# connecting.net
KiCad netlist of a schematic drawn in EAGLE
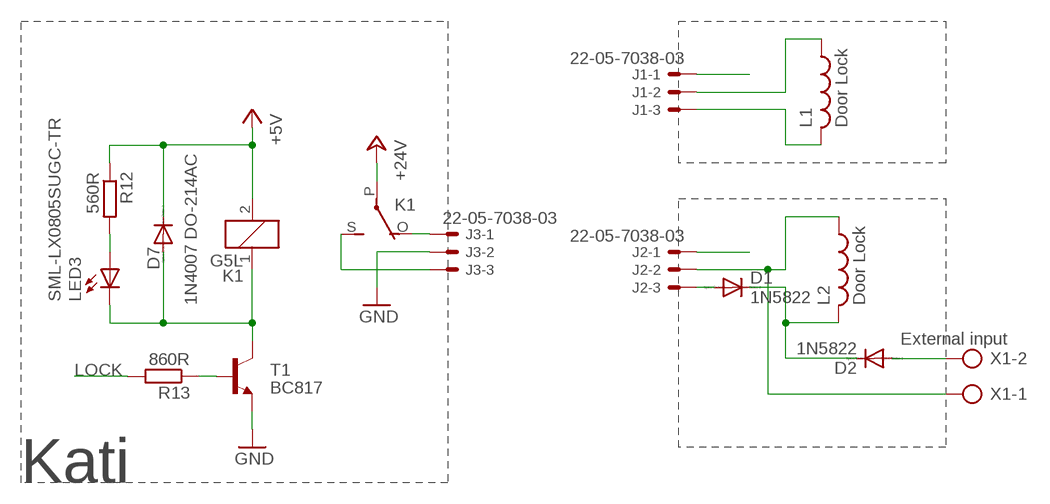
[diagram p0: schematic, sheet 1]

(export (version "E")
  (design (tool "Eeschema 10.0.6"))
  (components
    (comp (ref "D1")
      (value "1N5822")
      (footprint "eagle-import:DO204-10")
      (libsource (lib "eagle-import") (part "1N5059"))
    )
    (comp (ref "D2")
      (value "1N5822")
      (footprint "eagle-import:DO204-10")
      (libsource (lib "eagle-import") (part "1N5059"))
    )
    (comp (ref "D7")
      (value "1N4007 DO-214AC")
      (footprint "eagle-import:DO-214AC")
      (libsource (lib "eagle-import") (part "DIODE-DO-214AC"))
    )
    (comp (ref "J1")
      (value "22-05-7038-03")
      (footprint "eagle-import:7395-03")
      (libsource (lib "eagle-import") (part "22-?-0305-7038"))
    )
    (comp (ref "J2")
      (value "22-05-7038-03")
      (footprint "eagle-import:7395-03")
      (libsource (lib "eagle-import") (part "22-?-0305-7038"))
    )
    (comp (ref "J3")
      (value "22-05-7038-03")
      (footprint "eagle-import:7395-03")
      (libsource (lib "eagle-import") (part "22-?-0305-7038"))
    )
    (comp (ref "K1")
      (value "G5L")
      (footprint "eagle-import:G5LE")
      (libsource (lib "eagle-import") (part "G5L"))
    )
    (comp (ref "L1")
      (value "Door Lock")
      (footprint "eagle-import:0204_5")
      (libsource (lib "eagle-import") (part "L-US0204/5"))
    )
    (comp (ref "L2")
      (value "Door Lock")
      (footprint "eagle-import:0204_5")
      (libsource (lib "eagle-import") (part "L-US0204/5"))
    )
    (comp (ref "LED3")
      (value "SML-LX0805SUGC-TR")
      (footprint "eagle-import:CHIPLED_0805")
      (libsource (lib "eagle-import") (part "LEDCHIPLED_0805"))
    )
    (comp (ref "R12")
      (value "560R")
      (footprint "eagle-import:R0805")
      (libsource (lib "eagle-import") (part "R-EU_R0805"))
    )
    (comp (ref "R13")
      (value "860R")
      (footprint "eagle-import:R0805")
      (libsource (lib "eagle-import") (part "R-EU_R0805"))
    )
    (comp (ref "T1")
      (value "BC817")
      (footprint "eagle-import:SOT23-BEC")
      (libsource (lib "eagle-import") (part "-NPN-SOT23-BECBC817-16"))
    )
    (comp (ref "X1")
      (value "External input")
      (footprint "eagle-import:AK300_2")
      (libsource (lib "eagle-import") (part "AK300/2"))
    )
  )
  (nets
    (net (code "1") (name "+5V") (class "Default")
      (node (ref "D7") (pin "C") (pinfunction "C_C") (pintype "passive"))
      (node (ref "K1") (pin "2") (pinfunction "2_2") (pintype "passive"))
      (node (ref "R12") (pin "1") (pinfunction "1_1") (pintype "passive"))
    )
    (net (code "2") (name "+24V") (class "Default")
      (node (ref "K1") (pin "P") (pinfunction "P_P") (pintype "passive"))
    )
    (net (code "3") (name "/LOCK") (class "Default")
      (node (ref "R13") (pin "2") (pinfunction "2_2") (pintype "passive"))
    )
    (net (code "4") (name "GND") (class "Default")
      (node (ref "J3") (pin "2") (pinfunction "S_2") (pintype "passive"))
      (node (ref "T1") (pin "E") (pinfunction "E_E") (pintype "passive"))
    )
    (net (code "5") (name "Net-(D1-PadC)") (class "Default")
      (node (ref "D1") (pin "C") (pinfunction "C_C") (pintype "passive"))
      (node (ref "D2") (pin "C") (pinfunction "C_C") (pintype "passive"))
      (node (ref "L2") (pin "2") (pinfunction "2_2") (pintype "passive"))
    )
    (net (code "6") (name "Net-(D7-PadA)") (class "Default")
      (node (ref "D7") (pin "A") (pinfunction "A_A") (pintype "passive"))
      (node (ref "K1") (pin "1") (pinfunction "1_1") (pintype "passive"))
      (node (ref "LED3") (pin "C") (pinfunction "C_C") (pintype "passive"))
      (node (ref "T1") (pin "C") (pinfunction "C_C") (pintype "passive"))
    )
    (net (code "7") (name "Net-(J1B-S)") (class "Default")
      (node (ref "J1") (pin "2") (pinfunction "S_2") (pintype "passive"))
      (node (ref "L1") (pin "1") (pinfunction "1_1") (pintype "passive"))
    )
    (net (code "8") (name "Net-(J1C-S)") (class "Default")
      (node (ref "J1") (pin "3") (pinfunction "S_3") (pintype "passive"))
      (node (ref "L1") (pin "2") (pinfunction "2_2") (pintype "passive"))
    )
    (net (code "9") (name "Net-(J2B-S)") (class "Default")
      (node (ref "J2") (pin "2") (pinfunction "S_2") (pintype "passive"))
      (node (ref "L2") (pin "1") (pinfunction "1_1") (pintype "passive"))
      (node (ref "X1") (pin "1") (pinfunction "KL_1") (pintype "passive"))
    )
    (net (code "10") (name "Net-(J2C-S)") (class "Default")
      (node (ref "D1") (pin "A") (pinfunction "A_A") (pintype "passive"))
      (node (ref "J2") (pin "3") (pinfunction "S_3") (pintype "passive"))
    )
    (net (code "11") (name "Net-(J3A-S)") (class "Default")
      (node (ref "J3") (pin "1") (pinfunction "S_1") (pintype "passive"))
      (node (ref "K1") (pin "O") (pinfunction "O_O") (pintype "passive"))
    )
    (net (code "12") (name "Net-(J3C-S)") (class "Default")
      (node (ref "J3") (pin "3") (pinfunction "S_3") (pintype "passive"))
      (node (ref "K1") (pin "S") (pinfunction "S_S") (pintype "passive"))
    )
    (net (code "13") (name "Net-(LED3-PadA)") (class "Default")
      (node (ref "LED3") (pin "A") (pinfunction "A_A") (pintype "passive"))
      (node (ref "R12") (pin "2") (pinfunction "2_2") (pintype "passive"))
    )
    (net (code "14") (name "Net-(R13-Pad1)") (class "Default")
      (node (ref "R13") (pin "1") (pinfunction "1_1") (pintype "passive"))
      (node (ref "T1") (pin "B") (pinfunction "B_B") (pintype "passive"))
    )
    (net (code "15") (name "Net-(X1B-KL)") (class "Default")
      (node (ref "D2") (pin "A") (pinfunction "A_A") (pintype "passive"))
      (node (ref "X1") (pin "2") (pinfunction "KL_2") (pintype "passive"))
    )
    (net (code "16") (name "unconnected-(J1A-S-Pad1)") (class "Default")
      (node (ref "J1") (pin "1") (pinfunction "S_1") (pintype "passive"))
    )
    (net (code "17") (name "unconnected-(J2A-S-Pad1)") (class "Default")
      (node (ref "J2") (pin "1") (pinfunction "S_1") (pintype "passive"))
    )
  )
)
